# MinoControl.net
KiCad netlist of a schematic drawn in EAGLE
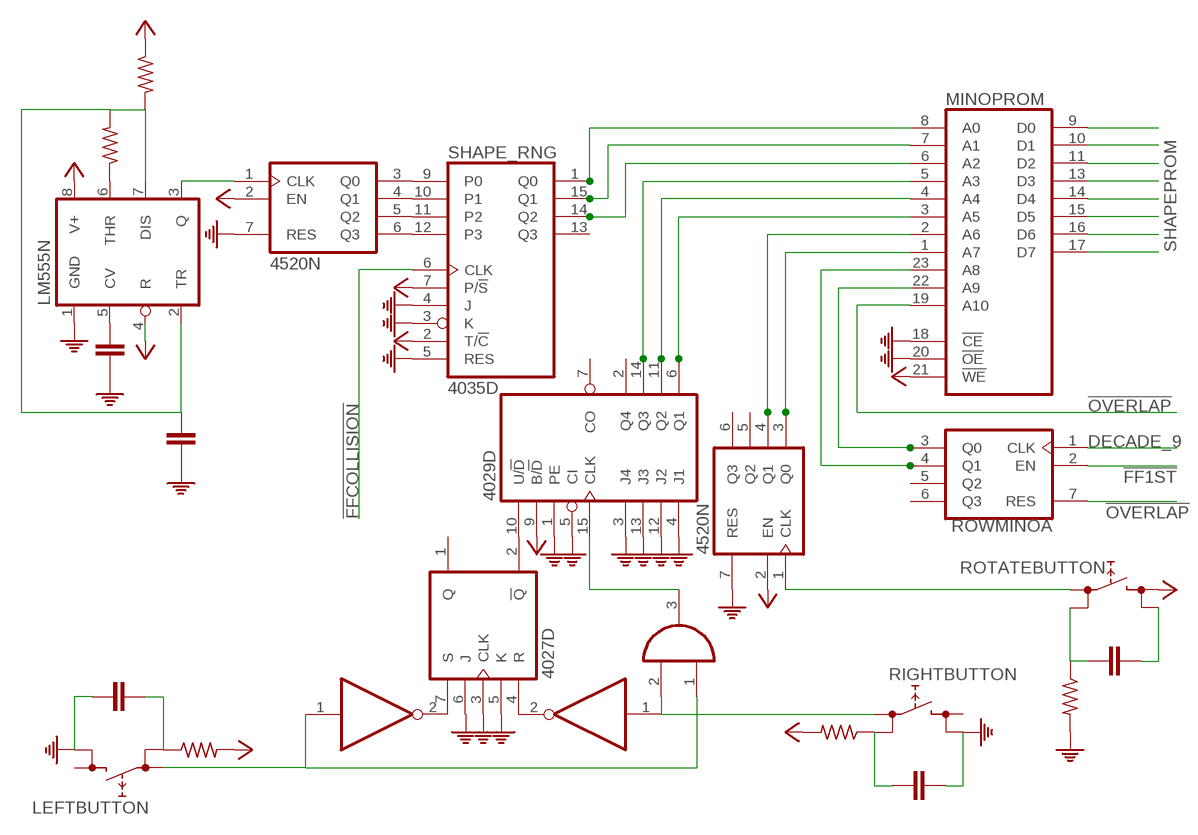
[diagram p0: schematic, sheet 1]

(export (version "E")
  (design (tool "Eeschema 10.0.6"))
  (components
    (comp (ref "IC1")
      (value "LM555N")
      (footprint "eagle-import:DIL08")
      (libsource (lib "eagle-import") (part "555NLM"))
    )
    (comp (ref "IC2")
      (value "4069D")
      (footprint "eagle-import:SO14")
      (libsource (lib "eagle-import") (part "4069D"))
    )
    (comp (ref "IC3")
      (value "4069D")
      (footprint "eagle-import:SO14")
      (libsource (lib "eagle-import") (part "4069D"))
    )
    (comp (ref "IC4")
      (value "4520N")
      (footprint "eagle-import:DIL16")
      (libsource (lib "eagle-import") (part "4520N"))
    )
    (comp (ref "IC5")
      (value "4027D")
      (footprint "eagle-import:SO16")
      (libsource (lib "eagle-import") (part "4027D"))
    )
    (comp (ref "IC6")
      (value "4029D")
      (footprint "eagle-import:SO16")
      (libsource (lib "eagle-import") (part "4029D"))
    )
    (comp (ref "IC7")
      (value "4081D")
      (footprint "eagle-import:SO14")
      (libsource (lib "eagle-import") (part "4081D"))
    )
    (comp (ref "IC8")
      (value "4520N")
      (footprint "eagle-import:DIL16")
      (libsource (lib "eagle-import") (part "4520N"))
    )
    (comp (ref "LEFTBUTTON")
      (value "REKN")
      (footprint "eagle-import:REKN")
      (libsource (lib "eagle-import") (part "REKN"))
    )
    (comp (ref "MINOPROM")
      (value "2816")
      (footprint "eagle-import:DIL24")
      (libsource (lib "eagle-import") (part "2816"))
    )
    (comp (ref "R1")
      (value "R-US_0204/7")
      (footprint "eagle-import:0204_7")
      (libsource (lib "eagle-import") (part "R-US_0204/7"))
    )
    (comp (ref "R2")
      (value "R-US_0204/7")
      (footprint "eagle-import:0204_7")
      (libsource (lib "eagle-import") (part "R-US_0204/7"))
    )
    (comp (ref "R3")
      (value "R-US_0204/7")
      (footprint "eagle-import:0204_7")
      (libsource (lib "eagle-import") (part "R-US_0204/7"))
    )
    (comp (ref "R4")
      (value "R-US_0204/7")
      (footprint "eagle-import:0204_7")
      (libsource (lib "eagle-import") (part "R-US_0204/7"))
    )
    (comp (ref "R5")
      (value "R-US_0204/7")
      (footprint "eagle-import:0204_7")
      (libsource (lib "eagle-import") (part "R-US_0204/7"))
    )
    (comp (ref "RIGHTBUTTON")
      (value "REKN")
      (footprint "eagle-import:REKN")
      (libsource (lib "eagle-import") (part "REKN"))
    )
    (comp (ref "ROTATEBUTTON")
      (value "REKN")
      (footprint "eagle-import:REKN")
      (libsource (lib "eagle-import") (part "REKN"))
    )
    (comp (ref "ROWMINO")
      (value "4520N")
      (footprint "eagle-import:DIL16")
      (libsource (lib "eagle-import") (part "4520N"))
    )
    (comp (ref "SHAPE_RNG")
      (value "4035D")
      (footprint "eagle-import:SO16")
      (libsource (lib "eagle-import") (part "4035D"))
    )
  )
  (nets
    (net (code "1") (name "/DECADE_9") (class "Default")
      (node (ref "ROWMINO") (pin "1") (pinfunction "CLK_1") (pintype "input"))
    )
    (net (code "2") (name "/SHAPEPROM") (class "Default")
      (node (ref "MINOPROM") (pin "10") (pinfunction "D1_10") (pintype "bidirectional"))
    )
    (net (code "3") (name "/~{FF1ST}") (class "Default")
      (node (ref "ROWMINO") (pin "2") (pinfunction "EN_2") (pintype "input"))
    )
    (net (code "4") (name "/~{FFCOLLISION}") (class "Default")
      (node (ref "SHAPE_RNG") (pin "6") (pinfunction "CLK_6") (pintype "input"))
    )
    (net (code "5") (name "/~{OVERLAP}") (class "Default")
      (node (ref "MINOPROM") (pin "19") (pinfunction "A10_19") (pintype "input"))
      (node (ref "ROWMINO") (pin "7") (pinfunction "RES_7") (pintype "input"))
    )
    (net (code "6") (name "Net-(IC1-DIS)") (class "Default")
      (node (ref "IC1") (pin "2") (pinfunction "TR_2") (pintype "input"))
      (node (ref "IC1") (pin "7") (pinfunction "DIS_7") (pintype "input"))
      (node (ref "R4") (pin "2") (pinfunction "2_2") (pintype "passive"))
      (node (ref "R5") (pin "2") (pinfunction "2_2") (pintype "passive"))
    )
    (net (code "7") (name "Net-(IC1-Q)") (class "Default")
      (node (ref "IC1") (pin "3") (pinfunction "Q_3") (pintype "output"))
      (node (ref "IC8") (pin "1") (pinfunction "CLK_1") (pintype "input"))
    )
    (net (code "8") (name "Net-(IC1-THR)") (class "Default")
      (node (ref "IC1") (pin "6") (pinfunction "THR_6") (pintype "input"))
      (node (ref "R5") (pin "1") (pinfunction "1_1") (pintype "passive"))
    )
    (net (code "9") (name "Net-(IC2A-I)") (class "Default")
      (node (ref "IC2") (pin "1") (pinfunction "I_1") (pintype "input"))
      (node (ref "IC7") (pin "1") (pinfunction "I0_1") (pintype "input"))
      (node (ref "LEFTBUTTON") (pin "0A") (pinfunction "0_0A") (pintype "passive"))
    )
    (net (code "10") (name "Net-(IC2A-O)") (class "Default")
      (node (ref "IC2") (pin "2") (pinfunction "O_2") (pintype "output"))
      (node (ref "IC5") (pin "7") (pinfunction "S_7") (pintype "input"))
    )
    (net (code "11") (name "Net-(IC3A-I)") (class "Default")
      (node (ref "IC3") (pin "1") (pinfunction "I_1") (pintype "input"))
      (node (ref "IC7") (pin "2") (pinfunction "I1_2") (pintype "input"))
      (node (ref "RIGHTBUTTON") (pin "0A") (pinfunction "0_0A") (pintype "passive"))
    )
    (net (code "12") (name "Net-(IC3A-O)") (class "Default")
      (node (ref "IC3") (pin "2") (pinfunction "O_2") (pintype "output"))
      (node (ref "IC5") (pin "4") (pinfunction "R_4") (pintype "input"))
    )
    (net (code "13") (name "Net-(IC4A-CLK)") (class "Default")
      (node (ref "IC4") (pin "1") (pinfunction "CLK_1") (pintype "input"))
      (node (ref "ROTATEBUTTON") (pin "0A") (pinfunction "0_0A") (pintype "passive"))
    )
    (net (code "14") (name "Net-(IC4A-Q0)") (class "Default")
      (node (ref "IC4") (pin "3") (pinfunction "Q0_3") (pintype "output"))
      (node (ref "MINOPROM") (pin "1") (pinfunction "A7_1") (pintype "input"))
    )
    (net (code "15") (name "Net-(IC4A-Q1)") (class "Default")
      (node (ref "IC4") (pin "4") (pinfunction "Q1_4") (pintype "output"))
      (node (ref "MINOPROM") (pin "2") (pinfunction "A6_2") (pintype "input"))
    )
    (net (code "16") (name "Net-(IC5A-~{Q})") (class "Default")
      (node (ref "IC5") (pin "2") (pinfunction "~{Q}_2") (pintype "output"))
      (node (ref "IC6") (pin "10") (pinfunction "U/~{D}_10") (pintype "input"))
    )
    (net (code "17") (name "Net-(IC6A-CLK)") (class "Default")
      (node (ref "IC6") (pin "15") (pinfunction "CLK_15") (pintype "input"))
      (node (ref "IC7") (pin "3") (pinfunction "O_3") (pintype "output"))
    )
    (net (code "18") (name "Net-(IC6A-Q1)") (class "Default")
      (node (ref "IC6") (pin "6") (pinfunction "Q1_6") (pintype "output"))
      (node (ref "MINOPROM") (pin "3") (pinfunction "A5_3") (pintype "input"))
    )
    (net (code "19") (name "Net-(IC6A-Q2)") (class "Default")
      (node (ref "IC6") (pin "11") (pinfunction "Q2_11") (pintype "output"))
      (node (ref "MINOPROM") (pin "4") (pinfunction "A4_4") (pintype "input"))
    )
    (net (code "20") (name "Net-(IC6A-Q3)") (class "Default")
      (node (ref "IC6") (pin "14") (pinfunction "Q3_14") (pintype "output"))
      (node (ref "MINOPROM") (pin "5") (pinfunction "A3_5") (pintype "input"))
    )
    (net (code "21") (name "Net-(IC8A-Q0)") (class "Default")
      (node (ref "IC8") (pin "3") (pinfunction "Q0_3") (pintype "output"))
      (node (ref "SHAPE_RNG") (pin "9") (pinfunction "P0_9") (pintype "input"))
    )
    (net (code "22") (name "Net-(IC8A-Q1)") (class "Default")
      (node (ref "IC8") (pin "4") (pinfunction "Q1_4") (pintype "output"))
      (node (ref "SHAPE_RNG") (pin "10") (pinfunction "P1_10") (pintype "input"))
    )
    (net (code "23") (name "Net-(IC8A-Q2)") (class "Default")
      (node (ref "IC8") (pin "5") (pinfunction "Q2_5") (pintype "output"))
      (node (ref "SHAPE_RNG") (pin "11") (pinfunction "P2_11") (pintype "input"))
    )
    (net (code "24") (name "Net-(IC8A-Q3)") (class "Default")
      (node (ref "IC8") (pin "6") (pinfunction "Q3_6") (pintype "output"))
      (node (ref "SHAPE_RNG") (pin "12") (pinfunction "P3_12") (pintype "input"))
    )
    (net (code "25") (name "Net-(LEFTBUTTON-0-Pad0B)") (class "Default")
      (node (ref "LEFTBUTTON") (pin "0B") (pinfunction "0_0B") (pintype "passive"))
      (node (ref "R1") (pin "1") (pinfunction "1_1") (pintype "passive"))
    )
    (net (code "26") (name "Net-(MINOPROMA-A0)") (class "Default")
      (node (ref "MINOPROM") (pin "8") (pinfunction "A0_8") (pintype "input"))
      (node (ref "SHAPE_RNG") (pin "1") (pinfunction "Q0_1") (pintype "output"))
    )
    (net (code "27") (name "Net-(MINOPROMA-A1)") (class "Default")
      (node (ref "MINOPROM") (pin "7") (pinfunction "A1_7") (pintype "input"))
      (node (ref "SHAPE_RNG") (pin "15") (pinfunction "Q1_15") (pintype "output"))
    )
    (net (code "28") (name "Net-(MINOPROMA-A2)") (class "Default")
      (node (ref "MINOPROM") (pin "6") (pinfunction "A2_6") (pintype "input"))
      (node (ref "SHAPE_RNG") (pin "14") (pinfunction "Q2_14") (pintype "output"))
    )
    (net (code "29") (name "Net-(MINOPROMA-A8)") (class "Default")
      (node (ref "MINOPROM") (pin "23") (pinfunction "A8_23") (pintype "input"))
      (node (ref "ROWMINO") (pin "4") (pinfunction "Q1_4") (pintype "output"))
    )
    (net (code "30") (name "Net-(MINOPROMA-A9)") (class "Default")
      (node (ref "MINOPROM") (pin "22") (pinfunction "A9_22") (pintype "input"))
      (node (ref "ROWMINO") (pin "3") (pinfunction "Q0_3") (pintype "output"))
    )
    (net (code "31") (name "Net-(R2-Pad1)") (class "Default")
      (node (ref "R2") (pin "1") (pinfunction "1_1") (pintype "passive"))
      (node (ref "ROTATEBUTTON") (pin "0B") (pinfunction "0_0B") (pintype "passive"))
    )
    (net (code "32") (name "Net-(R3-Pad1)") (class "Default")
      (node (ref "R3") (pin "1") (pinfunction "1_1") (pintype "passive"))
      (node (ref "RIGHTBUTTON") (pin "0B") (pinfunction "0_0B") (pintype "passive"))
    )
    (net (code "33") (name "PE") (class "Default")
      (node (ref "IC1") (pin "1") (pinfunction "GND_1") (pintype "power_in"))
      (node (ref "IC4") (pin "7") (pinfunction "RES_7") (pintype "input"))
      (node (ref "IC5") (pin "3") (pinfunction "CLK_3") (pintype "input"))
      (node (ref "IC5") (pin "5") (pinfunction "K_5") (pintype "input"))
      (node (ref "IC5") (pin "6") (pinfunction "J_6") (pintype "input"))
      (node (ref "IC6") (pin "1") (pinfunction "PE_1") (pintype "input"))
      (node (ref "IC6") (pin "12") (pinfunction "J2_12") (pintype "input"))
      (node (ref "IC6") (pin "13") (pinfunction "J3_13") (pintype "input"))
      (node (ref "IC6") (pin "3") (pinfunction "J4_3") (pintype "input"))
      (node (ref "IC6") (pin "4") (pinfunction "J1_4") (pintype "input"))
      (node (ref "IC6") (pin "5") (pinfunction "CI_5") (pintype "input"))
      (node (ref "IC8") (pin "7") (pinfunction "RES_7") (pintype "input"))
      (node (ref "LEFTBUTTON") (pin "1B") (pinfunction "1_1B") (pintype "passive"))
      (node (ref "MINOPROM") (pin "18") (pinfunction "~{CE}_18") (pintype "input"))
      (node (ref "MINOPROM") (pin "20") (pinfunction "~{OE}_20") (pintype "input"))
      (node (ref "R2") (pin "2") (pinfunction "2_2") (pintype "passive"))
      (node (ref "RIGHTBUTTON") (pin "1B") (pinfunction "1_1B") (pintype "passive"))
      (node (ref "SHAPE_RNG") (pin "3") (pinfunction "K_3") (pintype "input"))
      (node (ref "SHAPE_RNG") (pin "4") (pinfunction "J_4") (pintype "input"))
      (node (ref "SHAPE_RNG") (pin "5") (pinfunction "RES_5") (pintype "input"))
    )
    (net (code "34") (name "V+") (class "Default")
      (node (ref "IC1") (pin "4") (pinfunction "R_4") (pintype "input"))
      (node (ref "IC1") (pin "8") (pinfunction "V+_8") (pintype "power_in"))
      (node (ref "IC4") (pin "2") (pinfunction "EN_2") (pintype "input"))
      (node (ref "IC6") (pin "9") (pinfunction "B/~{D}_9") (pintype "input"))
      (node (ref "IC8") (pin "2") (pinfunction "EN_2") (pintype "input"))
      (node (ref "MINOPROM") (pin "21") (pinfunction "~{WE}_21") (pintype "input"))
      (node (ref "R1") (pin "2") (pinfunction "2_2") (pintype "passive"))
      (node (ref "R3") (pin "2") (pinfunction "2_2") (pintype "passive"))
      (node (ref "R4") (pin "1") (pinfunction "1_1") (pintype "passive"))
      (node (ref "ROTATEBUTTON") (pin "1A") (pinfunction "1_1A") (pintype "passive"))
      (node (ref "SHAPE_RNG") (pin "2") (pinfunction "T/~{C}_2") (pintype "input"))
      (node (ref "SHAPE_RNG") (pin "7") (pinfunction "P/~{S}_7") (pintype "input"))
    )
    (net (code "35") (name "unconnected-(IC1-CV-Pad5)") (class "Default")
      (node (ref "IC1") (pin "5") (pinfunction "CV_5") (pintype "input"))
    )
    (net (code "36") (name "unconnected-(IC4A-Q2-Pad5)") (class "Default")
      (node (ref "IC4") (pin "5") (pinfunction "Q2_5") (pintype "output"))
    )
    (net (code "37") (name "unconnected-(IC4A-Q3-Pad6)") (class "Default")
      (node (ref "IC4") (pin "6") (pinfunction "Q3_6") (pintype "output"))
    )
    (net (code "38") (name "unconnected-(IC5A-Q-Pad1)") (class "Default")
      (node (ref "IC5") (pin "1") (pinfunction "Q_1") (pintype "output"))
    )
    (net (code "39") (name "unconnected-(IC6A-CO-Pad7)") (class "Default")
      (node (ref "IC6") (pin "7") (pinfunction "CO_7") (pintype "output"))
    )
    (net (code "40") (name "unconnected-(IC6A-Q4-Pad2)") (class "Default")
      (node (ref "IC6") (pin "2") (pinfunction "Q4_2") (pintype "output"))
    )
    (net (code "41") (name "unconnected-(LEFTBUTTON-1-Pad1A)") (class "Default")
      (node (ref "LEFTBUTTON") (pin "1A") (pinfunction "1_1A") (pintype "passive"))
    )
    (net (code "42") (name "unconnected-(MINOPROMA-D0-Pad9)") (class "Default")
      (node (ref "MINOPROM") (pin "9") (pinfunction "D0_9") (pintype "bidirectional"))
    )
    (net (code "43") (name "unconnected-(MINOPROMA-D2-Pad11)") (class "Default")
      (node (ref "MINOPROM") (pin "11") (pinfunction "D2_11") (pintype "bidirectional"))
    )
    (net (code "44") (name "unconnected-(MINOPROMA-D3-Pad13)") (class "Default")
      (node (ref "MINOPROM") (pin "13") (pinfunction "D3_13") (pintype "bidirectional"))
    )
    (net (code "45") (name "unconnected-(MINOPROMA-D4-Pad14)") (class "Default")
      (node (ref "MINOPROM") (pin "14") (pinfunction "D4_14") (pintype "bidirectional"))
    )
    (net (code "46") (name "unconnected-(MINOPROMA-D5-Pad15)") (class "Default")
      (node (ref "MINOPROM") (pin "15") (pinfunction "D5_15") (pintype "bidirectional"))
    )
    (net (code "47") (name "unconnected-(MINOPROMA-D6-Pad16)") (class "Default")
      (node (ref "MINOPROM") (pin "16") (pinfunction "D6_16") (pintype "bidirectional"))
    )
    (net (code "48") (name "unconnected-(MINOPROMA-D7-Pad17)") (class "Default")
      (node (ref "MINOPROM") (pin "17") (pinfunction "D7_17") (pintype "bidirectional"))
    )
    (net (code "49") (name "unconnected-(RIGHTBUTTON-1-Pad1A)") (class "Default")
      (node (ref "RIGHTBUTTON") (pin "1A") (pinfunction "1_1A") (pintype "passive"))
    )
    (net (code "50") (name "unconnected-(ROTATEBUTTON-1-Pad1B)") (class "Default")
      (node (ref "ROTATEBUTTON") (pin "1B") (pinfunction "1_1B") (pintype "passive"))
    )
    (net (code "51") (name "unconnected-(ROWMINOA-Q2-Pad5)") (class "Default")
      (node (ref "ROWMINO") (pin "5") (pinfunction "Q2_5") (pintype "output"))
    )
    (net (code "52") (name "unconnected-(ROWMINOA-Q3-Pad6)") (class "Default")
      (node (ref "ROWMINO") (pin "6") (pinfunction "Q3_6") (pintype "output"))
    )
    (net (code "53") (name "unconnected-(SHAPE_RNGA-Q3-Pad13)") (class "Default")
      (node (ref "SHAPE_RNG") (pin "13") (pinfunction "Q3_13") (pintype "output"))
    )
  )
)
